# X8R_analog_sensor.net
KiCad netlist of a schematic drawn in EAGLE
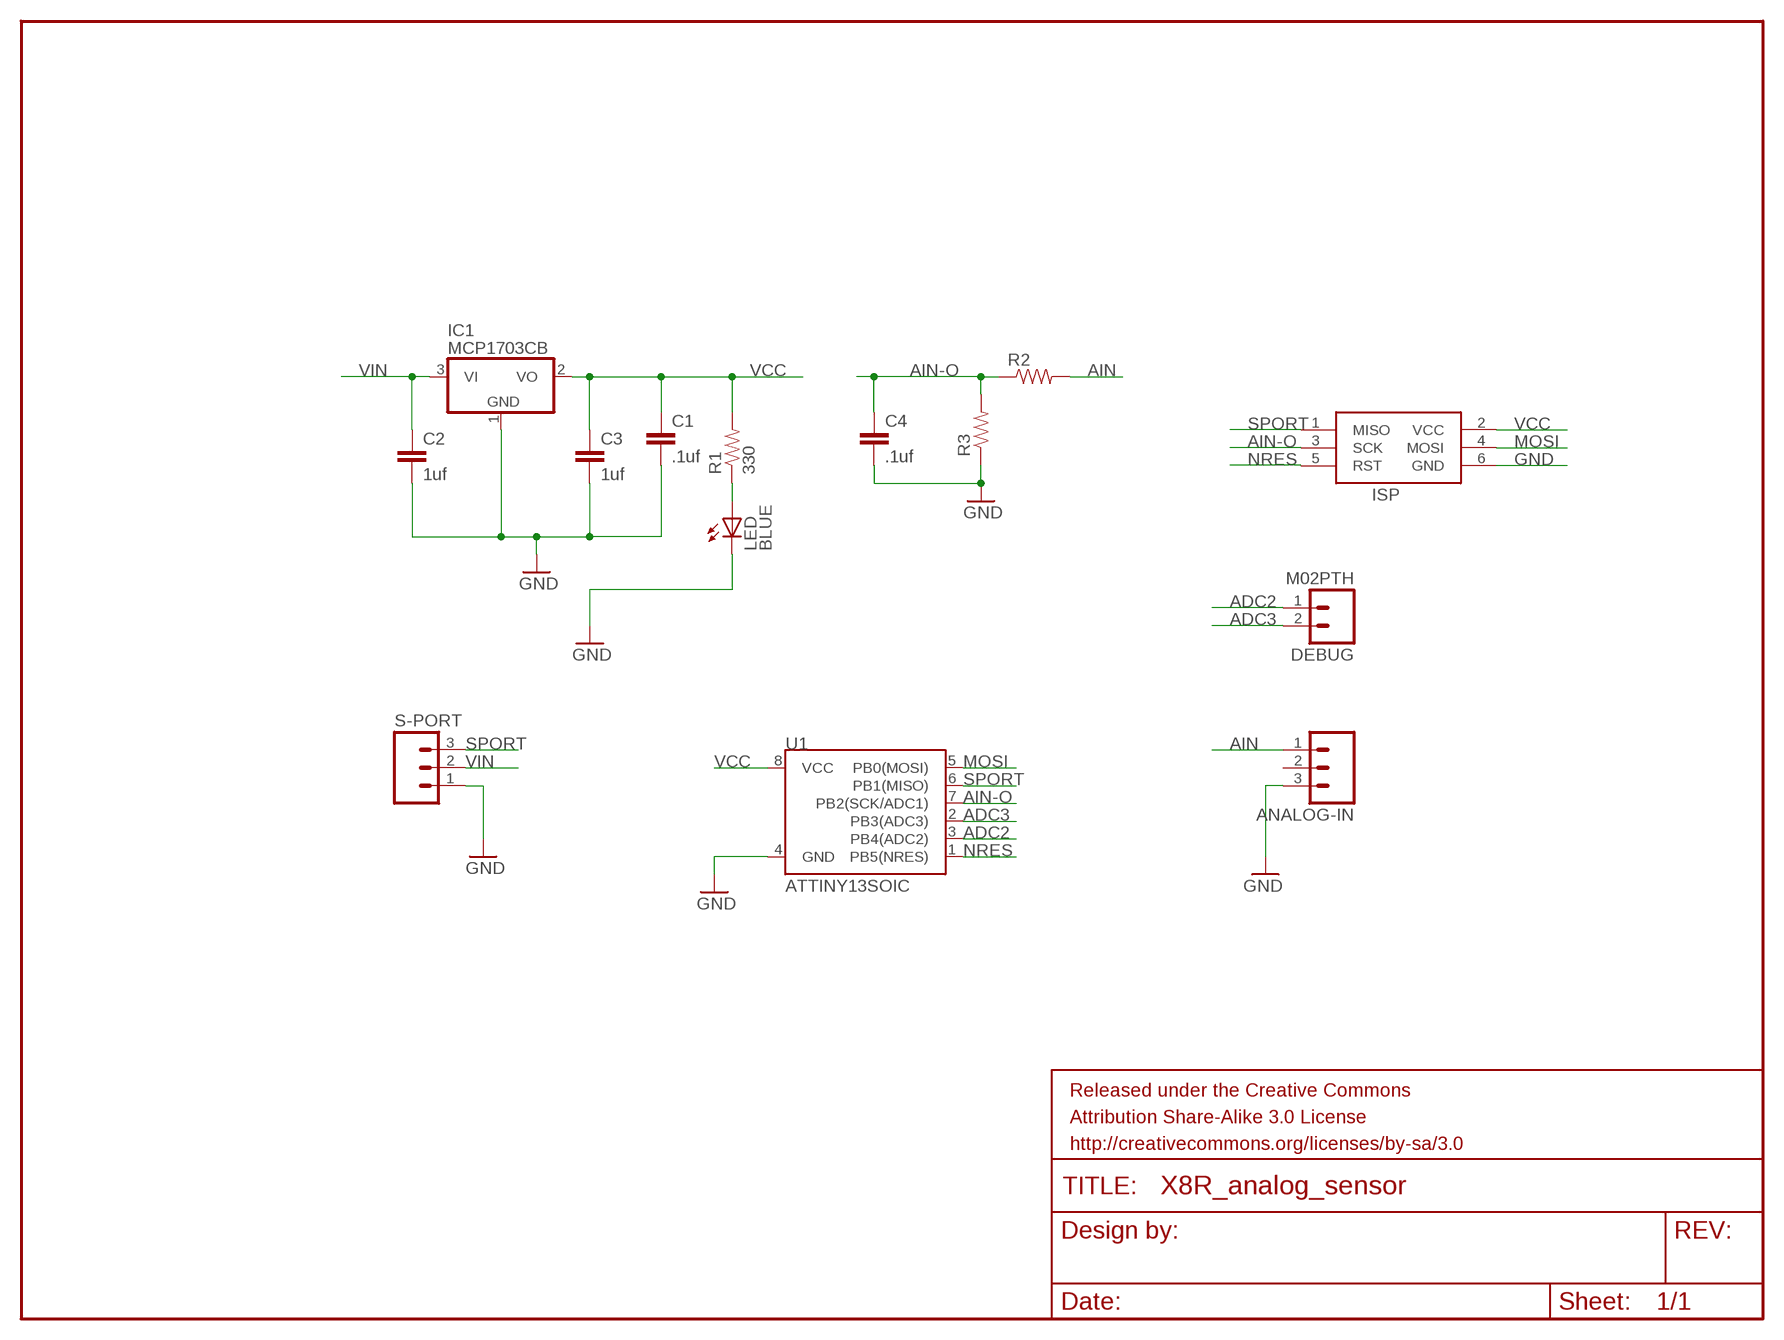
[diagram p0: schematic, sheet 1]

(export (version "E")
  (design (tool "Eeschema 10.0.6"))
  (components
    (comp (ref "ANALOG-IN")
      (value "M03PTH")
      (footprint "eagle-import:1X03")
      (libsource (lib "eagle-import") (part "M03PTH"))
    )
    (comp (ref "C1")
      (value ".1uf")
      (footprint "eagle-import:0603-CAP")
      (libsource (lib "eagle-import") (part "CAP0603-CAP"))
    )
    (comp (ref "C2")
      (value "1uf")
      (footprint "eagle-import:0603-CAP")
      (libsource (lib "eagle-import") (part "CAP0603-CAP"))
    )
    (comp (ref "C3")
      (value "1uf")
      (footprint "eagle-import:0603-CAP")
      (libsource (lib "eagle-import") (part "CAP0603-CAP"))
    )
    (comp (ref "C4")
      (value ".1uf")
      (footprint "eagle-import:0603-CAP")
      (libsource (lib "eagle-import") (part "CAP0603-CAP"))
    )
    (comp (ref "DEBUG")
      (value "M02PTH")
      (footprint "eagle-import:1X02")
      (libsource (lib "eagle-import") (part "M02PTH"))
    )
    (comp (ref "FRAME1")
      (value "FRAME-LETTER")
      (footprint "eagle-import:CREATIVE_COMMONS")
      (libsource (lib "eagle-import") (part "FRAME-LETTER"))
    )
    (comp (ref "IC1")
      (value "MCP1703CB")
      (footprint "eagle-import:SOT23")
      (libsource (lib "eagle-import") (part "MCP1703CB"))
    )
    (comp (ref "ISP")
      (value "AVRISP-6")
      (footprint "eagle-import:AVRISP")
      (libsource (lib "eagle-import") (part "AVRISP-6"))
    )
    (comp (ref "LED")
      (value "BLUE")
      (footprint "eagle-import:LED-0603")
      (libsource (lib "eagle-import") (part "LED0603"))
    )
    (comp (ref "R1")
      (value "330")
      (footprint "eagle-import:0603-RES")
      (libsource (lib "eagle-import") (part "RESISTOR0603"))
    )
    (comp (ref "R2")
      (value "RESISTORPTH-1/6W")
      (footprint "eagle-import:1_6W-RES")
      (libsource (lib "eagle-import") (part "RESISTORPTH-1/6W"))
    )
    (comp (ref "R3")
      (value "RESISTORPTH-1/6W")
      (footprint "eagle-import:1_6W-RES")
      (libsource (lib "eagle-import") (part "RESISTORPTH-1/6W"))
    )
    (comp (ref "S-PORT")
      (value "M03PTH")
      (footprint "eagle-import:1X03")
      (libsource (lib "eagle-import") (part "M03PTH"))
    )
    (comp (ref "U1")
      (value "ATTINY13SOIC")
      (footprint "eagle-import:SO08")
      (libsource (lib "eagle-import") (part "ATTINY13SOIC"))
    )
  )
  (nets
    (net (code "1") (name "/ADC2") (class "Default")
      (node (ref "DEBUG") (pin "1") (pinfunction "1_1") (pintype "passive"))
      (node (ref "U1") (pin "3") (pinfunction "PB4(ADC2)_3") (pintype "bidirectional"))
    )
    (net (code "2") (name "/ADC3") (class "Default")
      (node (ref "DEBUG") (pin "2") (pinfunction "2_2") (pintype "passive"))
      (node (ref "U1") (pin "2") (pinfunction "PB3(ADC3)_2") (pintype "bidirectional"))
    )
    (net (code "3") (name "/AIN") (class "Default")
      (node (ref "ANALOG-IN") (pin "1") (pinfunction "1_1") (pintype "passive"))
      (node (ref "R2") (pin "2") (pinfunction "2_2") (pintype "passive"))
    )
    (net (code "4") (name "/AIN-O") (class "Default")
      (node (ref "C4") (pin "1") (pinfunction "1_1") (pintype "passive"))
      (node (ref "ISP") (pin "3") (pinfunction "SCK_3") (pintype "output"))
      (node (ref "R2") (pin "1") (pinfunction "1_1") (pintype "passive"))
      (node (ref "R3") (pin "2") (pinfunction "2_2") (pintype "passive"))
      (node (ref "U1") (pin "7") (pinfunction "PB2(SCK/ADC1)_7") (pintype "bidirectional"))
    )
    (net (code "5") (name "/MOSI") (class "Default")
      (node (ref "ISP") (pin "4") (pinfunction "MOSI_4") (pintype "output"))
      (node (ref "U1") (pin "5") (pinfunction "PB0(MOSI)_5") (pintype "bidirectional"))
    )
    (net (code "6") (name "/NRES") (class "Default")
      (node (ref "ISP") (pin "5") (pinfunction "RST_5") (pintype "output"))
      (node (ref "U1") (pin "1") (pinfunction "PB5(NRES)_1") (pintype "bidirectional"))
    )
    (net (code "7") (name "/SPORT") (class "Default")
      (node (ref "ISP") (pin "1") (pinfunction "MISO_1") (pintype "input"))
      (node (ref "S-PORT") (pin "3") (pinfunction "3_3") (pintype "passive"))
      (node (ref "U1") (pin "6") (pinfunction "PB1(MISO)_6") (pintype "bidirectional"))
    )
    (net (code "8") (name "/VCC") (class "Default")
      (node (ref "C1") (pin "1") (pinfunction "1_1") (pintype "passive"))
      (node (ref "C3") (pin "1") (pinfunction "1_1") (pintype "passive"))
      (node (ref "IC1") (pin "2") (pinfunction "VO_2") (pintype "passive"))
      (node (ref "ISP") (pin "2") (pinfunction "VCC_2") (pintype "power_in"))
      (node (ref "R1") (pin "2") (pinfunction "2_2") (pintype "passive"))
      (node (ref "U1") (pin "8") (pinfunction "VCC_8") (pintype "bidirectional"))
    )
    (net (code "9") (name "/VIN") (class "Default")
      (node (ref "C2") (pin "1") (pinfunction "1_1") (pintype "passive"))
      (node (ref "IC1") (pin "3") (pinfunction "VI_3") (pintype "input"))
      (node (ref "S-PORT") (pin "2") (pinfunction "2_2") (pintype "passive"))
    )
    (net (code "10") (name "GND") (class "Default")
      (node (ref "ANALOG-IN") (pin "3") (pinfunction "3_3") (pintype "passive"))
      (node (ref "C1") (pin "2") (pinfunction "2_2") (pintype "passive"))
      (node (ref "C2") (pin "2") (pinfunction "2_2") (pintype "passive"))
      (node (ref "C3") (pin "2") (pinfunction "2_2") (pintype "passive"))
      (node (ref "C4") (pin "2") (pinfunction "2_2") (pintype "passive"))
      (node (ref "IC1") (pin "1") (pinfunction "GND_1") (pintype "passive"))
      (node (ref "ISP") (pin "6") (pinfunction "GND_6") (pintype "power_in"))
      (node (ref "LED") (pin "C") (pinfunction "C_C") (pintype "passive"))
      (node (ref "R3") (pin "1") (pinfunction "1_1") (pintype "passive"))
      (node (ref "S-PORT") (pin "1") (pinfunction "1_1") (pintype "passive"))
      (node (ref "U1") (pin "4") (pinfunction "GND_4") (pintype "bidirectional"))
    )
    (net (code "11") (name "Net-(LED-PadA)") (class "Default")
      (node (ref "LED") (pin "A") (pinfunction "A_A") (pintype "passive"))
      (node (ref "R1") (pin "1") (pinfunction "1_1") (pintype "passive"))
    )
    (net (code "12") (name "unconnected-(ANALOG-IN-Pad2)") (class "Default")
      (node (ref "ANALOG-IN") (pin "2") (pinfunction "2_2") (pintype "passive"))
    )
  )
)
